# RLD_and_screen.net
KiCad netlist of a schematic drawn in Altium Designer
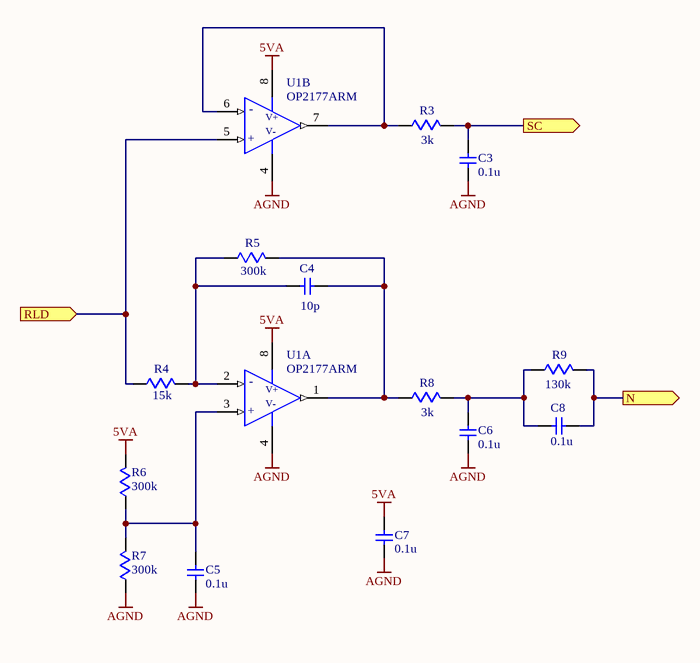
[diagram p0: RLD and screen.SchDoc]

(export (version "E")
  (design (tool "Eeschema 10.0.6"))
  (components
    (comp (ref "C3") (value "0.1u") (footprint "SMD/C/0603") (libsource (lib "My_lib") (part "Capacitor")))
    (comp (ref "C4") (value "10p") (footprint "SMD/C/0603") (libsource (lib "My_lib") (part "Capacitor")))
    (comp (ref "C5") (value "0.1u") (footprint "SMD/C/0603") (libsource (lib "My_lib") (part "Capacitor")))
    (comp (ref "C6") (value "0.1u") (footprint "SMD/C/0603") (libsource (lib "My_lib") (part "Capacitor")))
    (comp (ref "C7") (value "0.1u") (footprint "SMD/C/0603") (libsource (lib "My_lib") (part "Capacitor")))
    (comp (ref "C8") (value "0.1u") (footprint "SMD/C/0603") (libsource (lib "My_lib") (part "Capacitor")))
    (comp (ref "R3") (value "3k") (footprint "SMD/R/0603") (libsource (lib "My_lib") (part "Resistor")))
    (comp (ref "R4") (value "15k") (footprint "SMD/R/0603") (libsource (lib "My_lib") (part "Resistor")))
    (comp (ref "R5") (value "300k") (footprint "SMD/R/0603") (libsource (lib "My_lib") (part "Resistor")))
    (comp (ref "R6") (value "300k") (footprint "SMD/R/0603") (libsource (lib "My_lib") (part "Resistor")))
    (comp (ref "R7") (value "300k") (footprint "SMD/R/0603") (libsource (lib "My_lib") (part "Resistor")))
    (comp (ref "R8") (value "3k") (footprint "SMD/R/0603") (libsource (lib "My_lib") (part "Resistor")))
    (comp (ref "R9") (value "130k") (footprint "SMD/R/0603") (libsource (lib "My_lib") (part "Resistor")))
    (comp (ref "U1")
      (value "OP2177ARM")
      (footprint "SMD/SOP8/0.65MMP/3x3mm/4.9MMWP")
      (description "Precision Low Noise, Low Input Bias Current Operational Amplifiers")
      (libsource (lib "My_lib") (part "OP2177ARM"))
    )
  )
  (nets
    (net (code "1") (name "/N") (class "Default")
      (node (ref "C8") (pin "1") (pinfunction "1_1") (pintype "passive"))
      (node (ref "R9") (pin "2") (pinfunction "2_2") (pintype "passive"))
    )
    (net (code "2") (name "/RLD") (class "Default")
      (node (ref "R4") (pin "1") (pinfunction "1_1") (pintype "passive"))
      (node (ref "U1") (pin "5") (pinfunction "+_5") (pintype "input"))
    )
    (net (code "3") (name "/SC") (class "Default")
      (node (ref "C3") (pin "2") (pinfunction "2_2") (pintype "passive"))
      (node (ref "R3") (pin "2") (pinfunction "2_2") (pintype "passive"))
    )
    (net (code "4") (name "5VA") (class "Default")
      (node (ref "C7") (pin "2") (pinfunction "2_2") (pintype "passive"))
      (node (ref "R6") (pin "2") (pinfunction "2_2") (pintype "passive"))
      (node (ref "U1") (pin "8") (pinfunction "V+_8") (pintype "power_in"))
    )
    (net (code "5") (name "AGND") (class "Default")
      (node (ref "C3") (pin "1") (pinfunction "1_1") (pintype "passive"))
      (node (ref "C5") (pin "1") (pinfunction "1_1") (pintype "passive"))
      (node (ref "C6") (pin "1") (pinfunction "1_1") (pintype "passive"))
      (node (ref "C7") (pin "1") (pinfunction "1_1") (pintype "passive"))
      (node (ref "R7") (pin "1") (pinfunction "1_1") (pintype "passive"))
      (node (ref "U1") (pin "4") (pinfunction "V-_4") (pintype "power_in"))
    )
    (net (code "6") (name "Net-(C6-Pad2)") (class "Default")
      (node (ref "C6") (pin "2") (pinfunction "2_2") (pintype "passive"))
      (node (ref "C8") (pin "2") (pinfunction "2_2") (pintype "passive"))
      (node (ref "R8") (pin "2") (pinfunction "2_2") (pintype "passive"))
      (node (ref "R9") (pin "1") (pinfunction "1_1") (pintype "passive"))
    )
    (net (code "7") (name "Net-(U1A-+)") (class "Default")
      (node (ref "C5") (pin "2") (pinfunction "2_2") (pintype "passive"))
      (node (ref "R6") (pin "1") (pinfunction "1_1") (pintype "passive"))
      (node (ref "R7") (pin "2") (pinfunction "2_2") (pintype "passive"))
      (node (ref "U1") (pin "3") (pinfunction "+_3") (pintype "input"))
    )
    (net (code "8") (name "Net-(U1A--)") (class "Default")
      (node (ref "C4") (pin "2") (pinfunction "2_2") (pintype "passive"))
      (node (ref "R4") (pin "2") (pinfunction "2_2") (pintype "passive"))
      (node (ref "R5") (pin "1") (pinfunction "1_1") (pintype "passive"))
      (node (ref "U1") (pin "2") (pinfunction "-_2") (pintype "input"))
    )
    (net (code "9") (name "Net-(U1A-OUT)") (class "Default")
      (node (ref "C4") (pin "1") (pinfunction "1_1") (pintype "passive"))
      (node (ref "R5") (pin "2") (pinfunction "2_2") (pintype "passive"))
      (node (ref "R8") (pin "1") (pinfunction "1_1") (pintype "passive"))
      (node (ref "U1") (pin "1") (pinfunction "OUT_1") (pintype "output"))
    )
    (net (code "10") (name "Net-(U1B--)") (class "Default")
      (node (ref "R3") (pin "1") (pinfunction "1_1") (pintype "passive"))
      (node (ref "U1") (pin "6") (pinfunction "-_6") (pintype "input"))
      (node (ref "U1") (pin "7") (pinfunction "OUT_7") (pintype "output"))
    )
  )
)
